# PSU-single-voltage.net
KiCad netlist of a schematic drawn in EAGLE
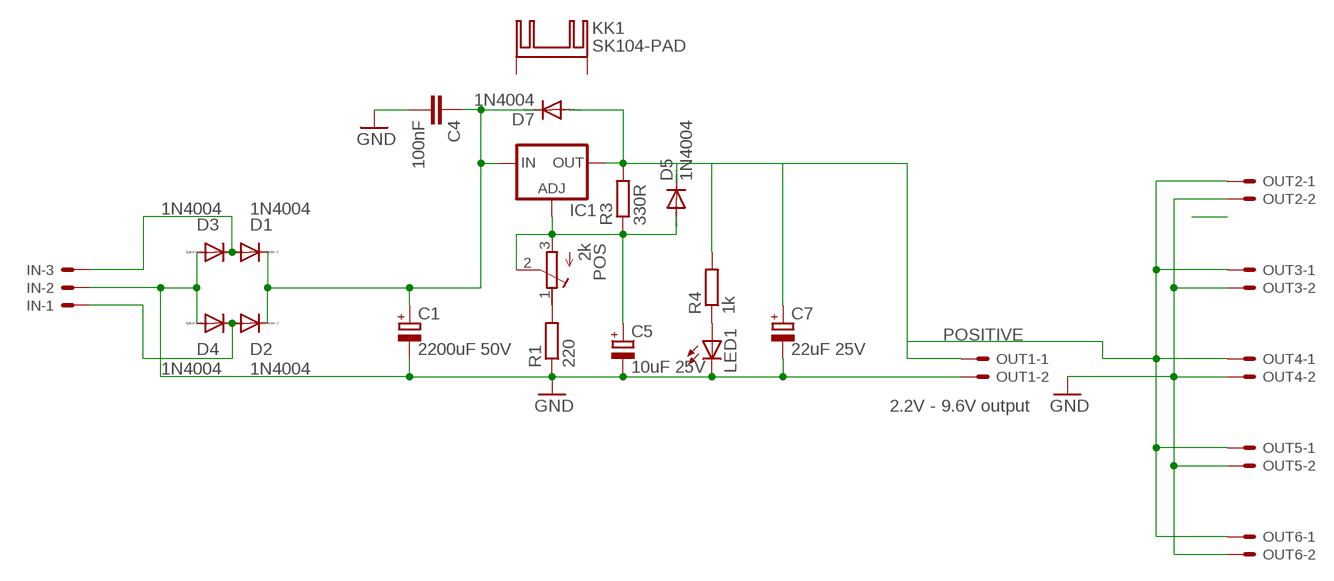
[diagram p0: schematic, sheet 1]

(export (version "E")
  (design (tool "Eeschema 10.0.6"))
  (components
    (comp (ref "C1")
      (value "2200uF 50V")
      (footprint "eagle-import:E7,5-16")
      (libsource (lib "eagle-import") (part "CPOL-EUE7.5-16"))
    )
    (comp (ref "C4")
      (value "100nF")
      (footprint "eagle-import:C050-025X075")
      (libsource (lib "eagle-import") (part "C-EU050-025X075"))
    )
    (comp (ref "C5")
      (value "10uF 25V")
      (footprint "eagle-import:E2,5-5")
      (libsource (lib "eagle-import") (part "CPOL-EUE2.5-5"))
    )
    (comp (ref "C7")
      (value "22uF 25V")
      (footprint "eagle-import:E2,5-5")
      (libsource (lib "eagle-import") (part "CPOL-EUE2.5-5"))
    )
    (comp (ref "D1")
      (value "1N4004")
      (footprint "eagle-import:DO41-10")
      (libsource (lib "eagle-import") (part "1N4004"))
    )
    (comp (ref "D2")
      (value "1N4004")
      (footprint "eagle-import:DO41-10")
      (libsource (lib "eagle-import") (part "1N4004"))
    )
    (comp (ref "D3")
      (value "1N4004")
      (footprint "eagle-import:DO41-10")
      (libsource (lib "eagle-import") (part "1N4004"))
    )
    (comp (ref "D4")
      (value "1N4004")
      (footprint "eagle-import:DO41-10")
      (libsource (lib "eagle-import") (part "1N4004"))
    )
    (comp (ref "D5")
      (value "1N4004")
      (footprint "eagle-import:DO41-10")
      (libsource (lib "eagle-import") (part "1N4004"))
    )
    (comp (ref "D7")
      (value "1N4004")
      (footprint "eagle-import:DO41-10")
      (libsource (lib "eagle-import") (part "1N4004"))
    )
    (comp (ref "IC1")
      (value "LM317TS")
      (footprint "eagle-import:317TS")
      (libsource (lib "eagle-import") (part "LM317TS"))
    )
    (comp (ref "IN")
      (value "KK-156-3")
      (footprint "eagle-import:KK-156-3")
      (libsource (lib "eagle-import") (part "KK-156-3"))
    )
    (comp (ref "KK1")
      (value "SK104-PAD")
      (footprint "eagle-import:SK104-PAD")
      (libsource (lib "eagle-import") (part "SK104-PAD"))
    )
    (comp (ref "LED1")
      (value "LED3MM")
      (footprint "eagle-import:LED3MM")
      (libsource (lib "eagle-import") (part "LED3MM"))
    )
    (comp (ref "OUT1")
      (value "KK-156-2")
      (footprint "eagle-import:KK-156-2")
      (libsource (lib "eagle-import") (part "KK-156-2"))
    )
    (comp (ref "OUT2")
      (value "KK-156-2")
      (footprint "eagle-import:KK-156-2")
      (libsource (lib "eagle-import") (part "KK-156-2"))
    )
    (comp (ref "OUT3")
      (value "KK-156-2")
      (footprint "eagle-import:KK-156-2")
      (libsource (lib "eagle-import") (part "KK-156-2"))
    )
    (comp (ref "OUT4")
      (value "KK-156-2")
      (footprint "eagle-import:KK-156-2")
      (libsource (lib "eagle-import") (part "KK-156-2"))
    )
    (comp (ref "OUT5")
      (value "KK-156-2")
      (footprint "eagle-import:KK-156-2")
      (libsource (lib "eagle-import") (part "KK-156-2"))
    )
    (comp (ref "OUT6")
      (value "KK-156-2")
      (footprint "eagle-import:KK-156-2")
      (libsource (lib "eagle-import") (part "KK-156-2"))
    )
    (comp (ref "POS")
      (value "2k")
      (footprint "eagle-import:RTRIMT93YA")
      (libsource (lib "eagle-import") (part "R-TRIMMT93YA"))
    )
    (comp (ref "R1")
      (value "220")
      (footprint "eagle-import:0207_7")
      (libsource (lib "eagle-import") (part "R-EU_0207/7"))
    )
    (comp (ref "R3")
      (value "330R")
      (footprint "eagle-import:0207_7")
      (libsource (lib "eagle-import") (part "R-EU_0207/7"))
    )
    (comp (ref "R4")
      (value "1k")
      (footprint "eagle-import:0207_7")
      (libsource (lib "eagle-import") (part "R-EU_0207/7"))
    )
  )
  (nets
    (net (code "1") (name "/POSITIVE") (class "Default")
      (node (ref "C7") (pin "+") (pinfunction "+_+") (pintype "passive"))
      (node (ref "D5") (pin "C") (pinfunction "C_C") (pintype "passive"))
      (node (ref "D7") (pin "A") (pinfunction "A_A") (pintype "passive"))
      (node (ref "IC1") (pin "2") (pinfunction "OUT_2") (pintype "passive"))
      (node (ref "OUT1") (pin "1") (pinfunction "S_1") (pintype "passive"))
      (node (ref "OUT2") (pin "1") (pinfunction "S_1") (pintype "passive"))
      (node (ref "OUT3") (pin "1") (pinfunction "S_1") (pintype "passive"))
      (node (ref "OUT4") (pin "1") (pinfunction "S_1") (pintype "passive"))
      (node (ref "OUT5") (pin "1") (pinfunction "S_1") (pintype "passive"))
      (node (ref "OUT6") (pin "1") (pinfunction "S_1") (pintype "passive"))
      (node (ref "R3") (pin "2") (pinfunction "2_2") (pintype "passive"))
      (node (ref "R4") (pin "2") (pinfunction "2_2") (pintype "passive"))
    )
    (net (code "2") (name "GND") (class "Default")
      (node (ref "C1") (pin "-") (pinfunction "-_-") (pintype "passive"))
      (node (ref "C4") (pin "2") (pinfunction "2_2") (pintype "passive"))
      (node (ref "C5") (pin "-") (pinfunction "-_-") (pintype "passive"))
      (node (ref "C7") (pin "-") (pinfunction "-_-") (pintype "passive"))
      (node (ref "D3") (pin "A") (pinfunction "A_A") (pintype "passive"))
      (node (ref "D4") (pin "A") (pinfunction "A_A") (pintype "passive"))
      (node (ref "IN") (pin "2") (pinfunction "S_2") (pintype "passive"))
      (node (ref "LED1") (pin "K") (pinfunction "C_K") (pintype "passive"))
      (node (ref "OUT1") (pin "2") (pinfunction "S_2") (pintype "passive"))
      (node (ref "OUT2") (pin "2") (pinfunction "S_2") (pintype "passive"))
      (node (ref "OUT3") (pin "2") (pinfunction "S_2") (pintype "passive"))
      (node (ref "OUT4") (pin "2") (pinfunction "S_2") (pintype "passive"))
      (node (ref "OUT5") (pin "2") (pinfunction "S_2") (pintype "passive"))
      (node (ref "OUT6") (pin "2") (pinfunction "S_2") (pintype "passive"))
      (node (ref "R1") (pin "1") (pinfunction "1_1") (pintype "passive"))
    )
    (net (code "3") (name "Net-(IC1-ADJ)") (class "Default")
      (node (ref "C5") (pin "+") (pinfunction "+_+") (pintype "passive"))
      (node (ref "D5") (pin "A") (pinfunction "A_A") (pintype "passive"))
      (node (ref "IC1") (pin "1") (pinfunction "ADJ_1") (pintype "input"))
      (node (ref "POS") (pin "2") (pinfunction "S_2") (pintype "passive"))
      (node (ref "POS") (pin "3") (pinfunction "A_3") (pintype "passive"))
      (node (ref "R3") (pin "1") (pinfunction "1_1") (pintype "passive"))
    )
    (net (code "4") (name "Net-(IC1-IN)") (class "Default")
      (node (ref "C1") (pin "+") (pinfunction "+_+") (pintype "passive"))
      (node (ref "C4") (pin "1") (pinfunction "1_1") (pintype "passive"))
      (node (ref "D1") (pin "C") (pinfunction "C_C") (pintype "passive"))
      (node (ref "D2") (pin "C") (pinfunction "C_C") (pintype "passive"))
      (node (ref "D7") (pin "C") (pinfunction "C_C") (pintype "passive"))
      (node (ref "IC1") (pin "3") (pinfunction "IN_3") (pintype "input"))
    )
    (net (code "5") (name "Net-(INA-S)") (class "Default")
      (node (ref "D2") (pin "A") (pinfunction "A_A") (pintype "passive"))
      (node (ref "D4") (pin "C") (pinfunction "C_C") (pintype "passive"))
      (node (ref "IN") (pin "1") (pinfunction "S_1") (pintype "passive"))
    )
    (net (code "6") (name "Net-(INC-S)") (class "Default")
      (node (ref "D1") (pin "A") (pinfunction "A_A") (pintype "passive"))
      (node (ref "D3") (pin "C") (pinfunction "C_C") (pintype "passive"))
      (node (ref "IN") (pin "3") (pinfunction "S_3") (pintype "passive"))
    )
    (net (code "7") (name "Net-(LED1-PadA)") (class "Default")
      (node (ref "LED1") (pin "A") (pinfunction "A_A") (pintype "passive"))
      (node (ref "R4") (pin "1") (pinfunction "1_1") (pintype "passive"))
    )
    (net (code "8") (name "Net-(POS-E)") (class "Default")
      (node (ref "POS") (pin "1") (pinfunction "E_1") (pintype "passive"))
      (node (ref "R1") (pin "2") (pinfunction "2_2") (pintype "passive"))
    )
    (net (code "9") (name "unconnected-(KK1-K-PadK1)") (class "Default")
      (node (ref "KK1") (pin "K1") (pinfunction "K_K1") (pintype "passive"))
    )
    (net (code "10") (name "unconnected-(KK1-K-PadK2)") (class "Default")
      (node (ref "KK1") (pin "K2") (pinfunction "K_K2") (pintype "passive"))
    )
  )
)
